# pc_sensything_lite_v1_2.net
KiCad netlist of a schematic drawn in EAGLE
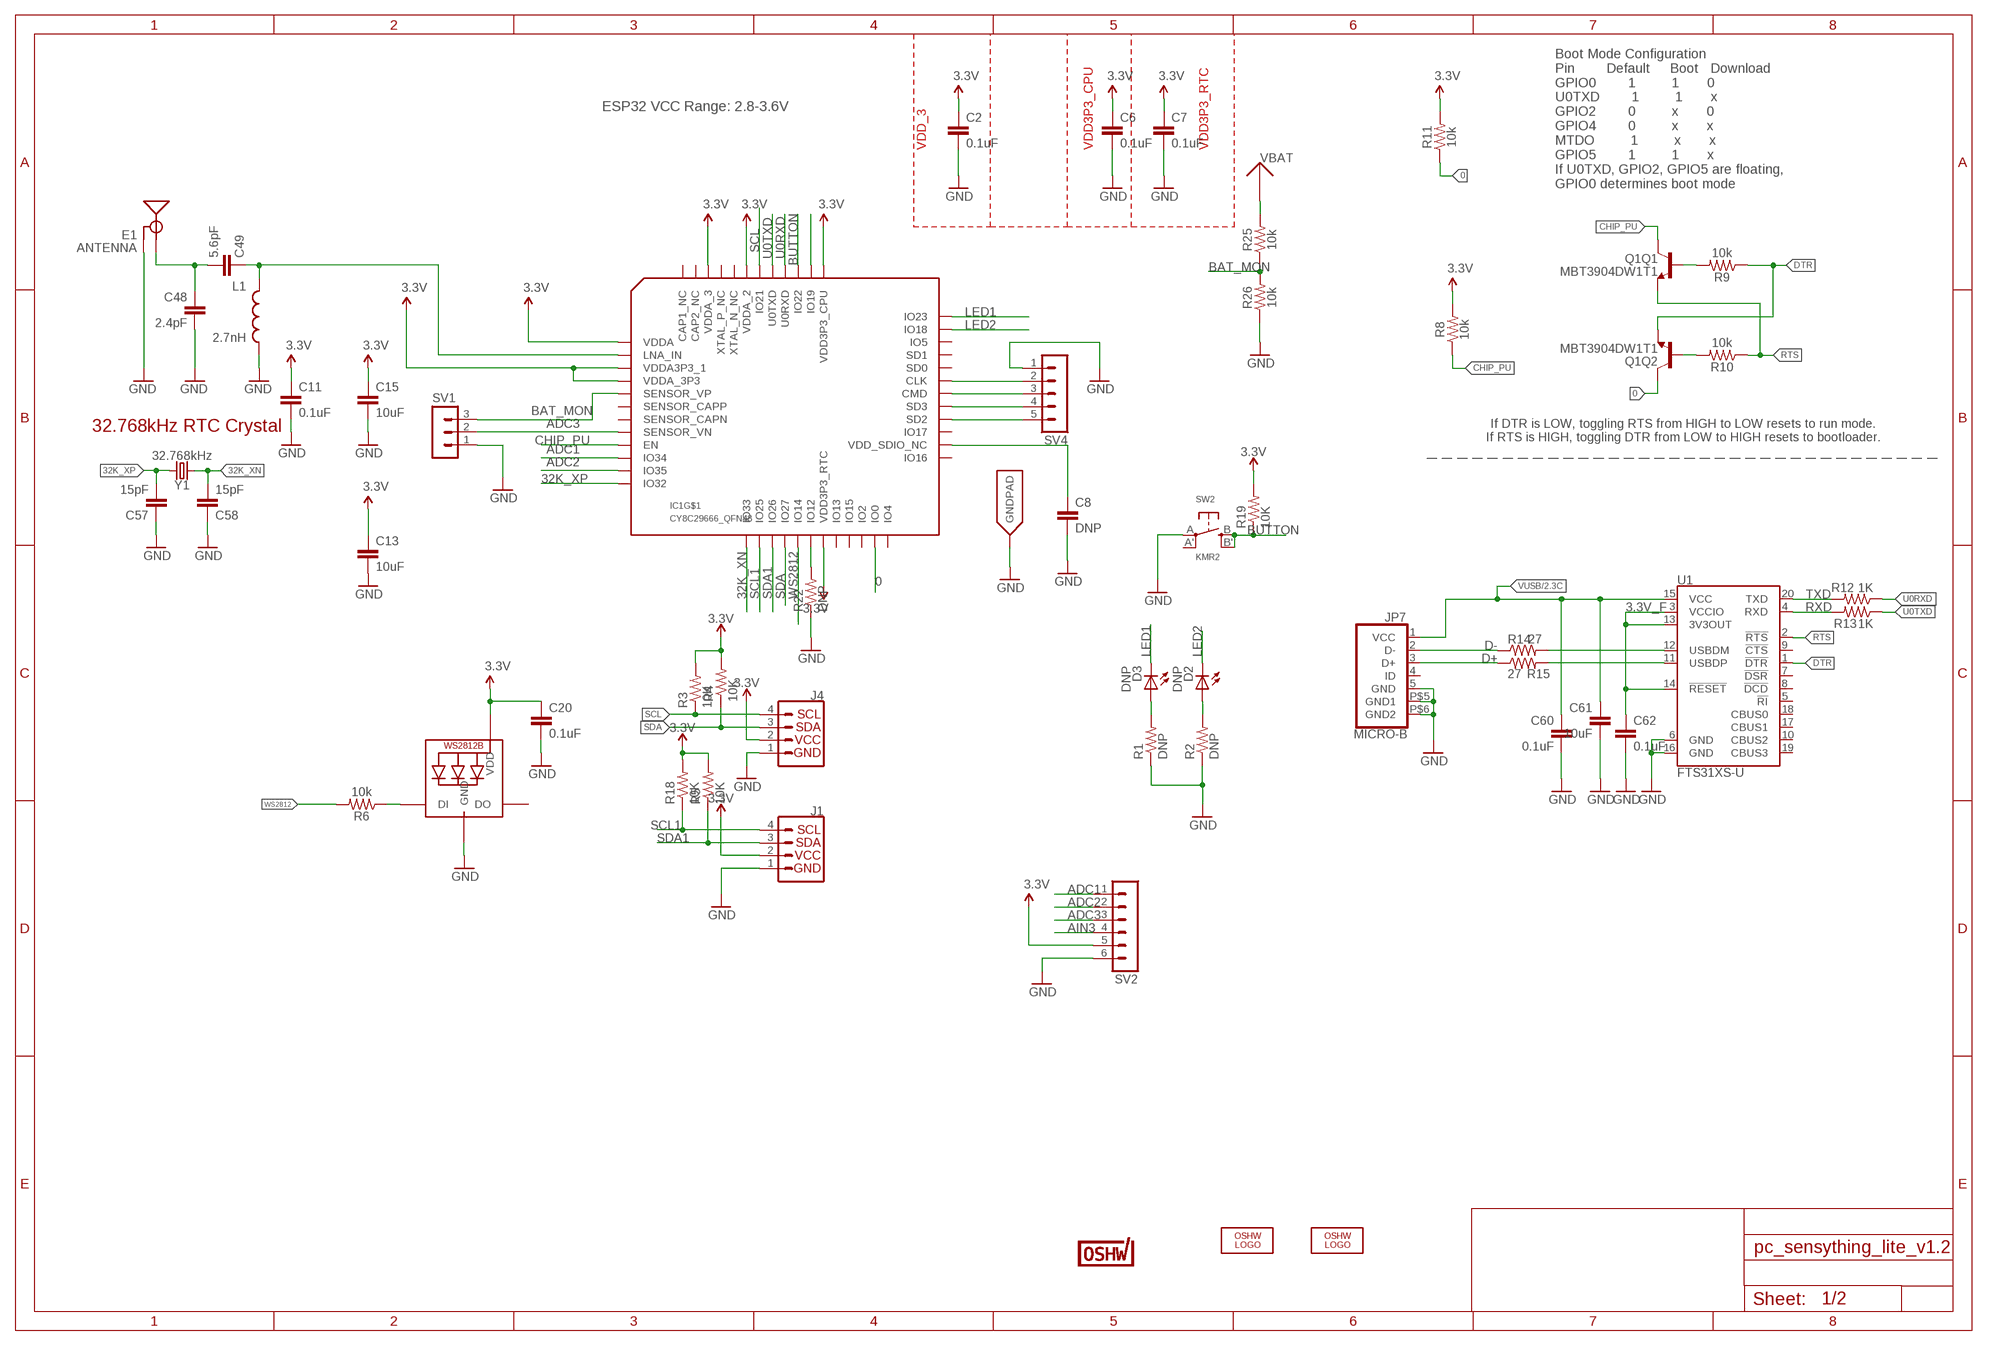
[diagram p0: schematic, sheet 1]
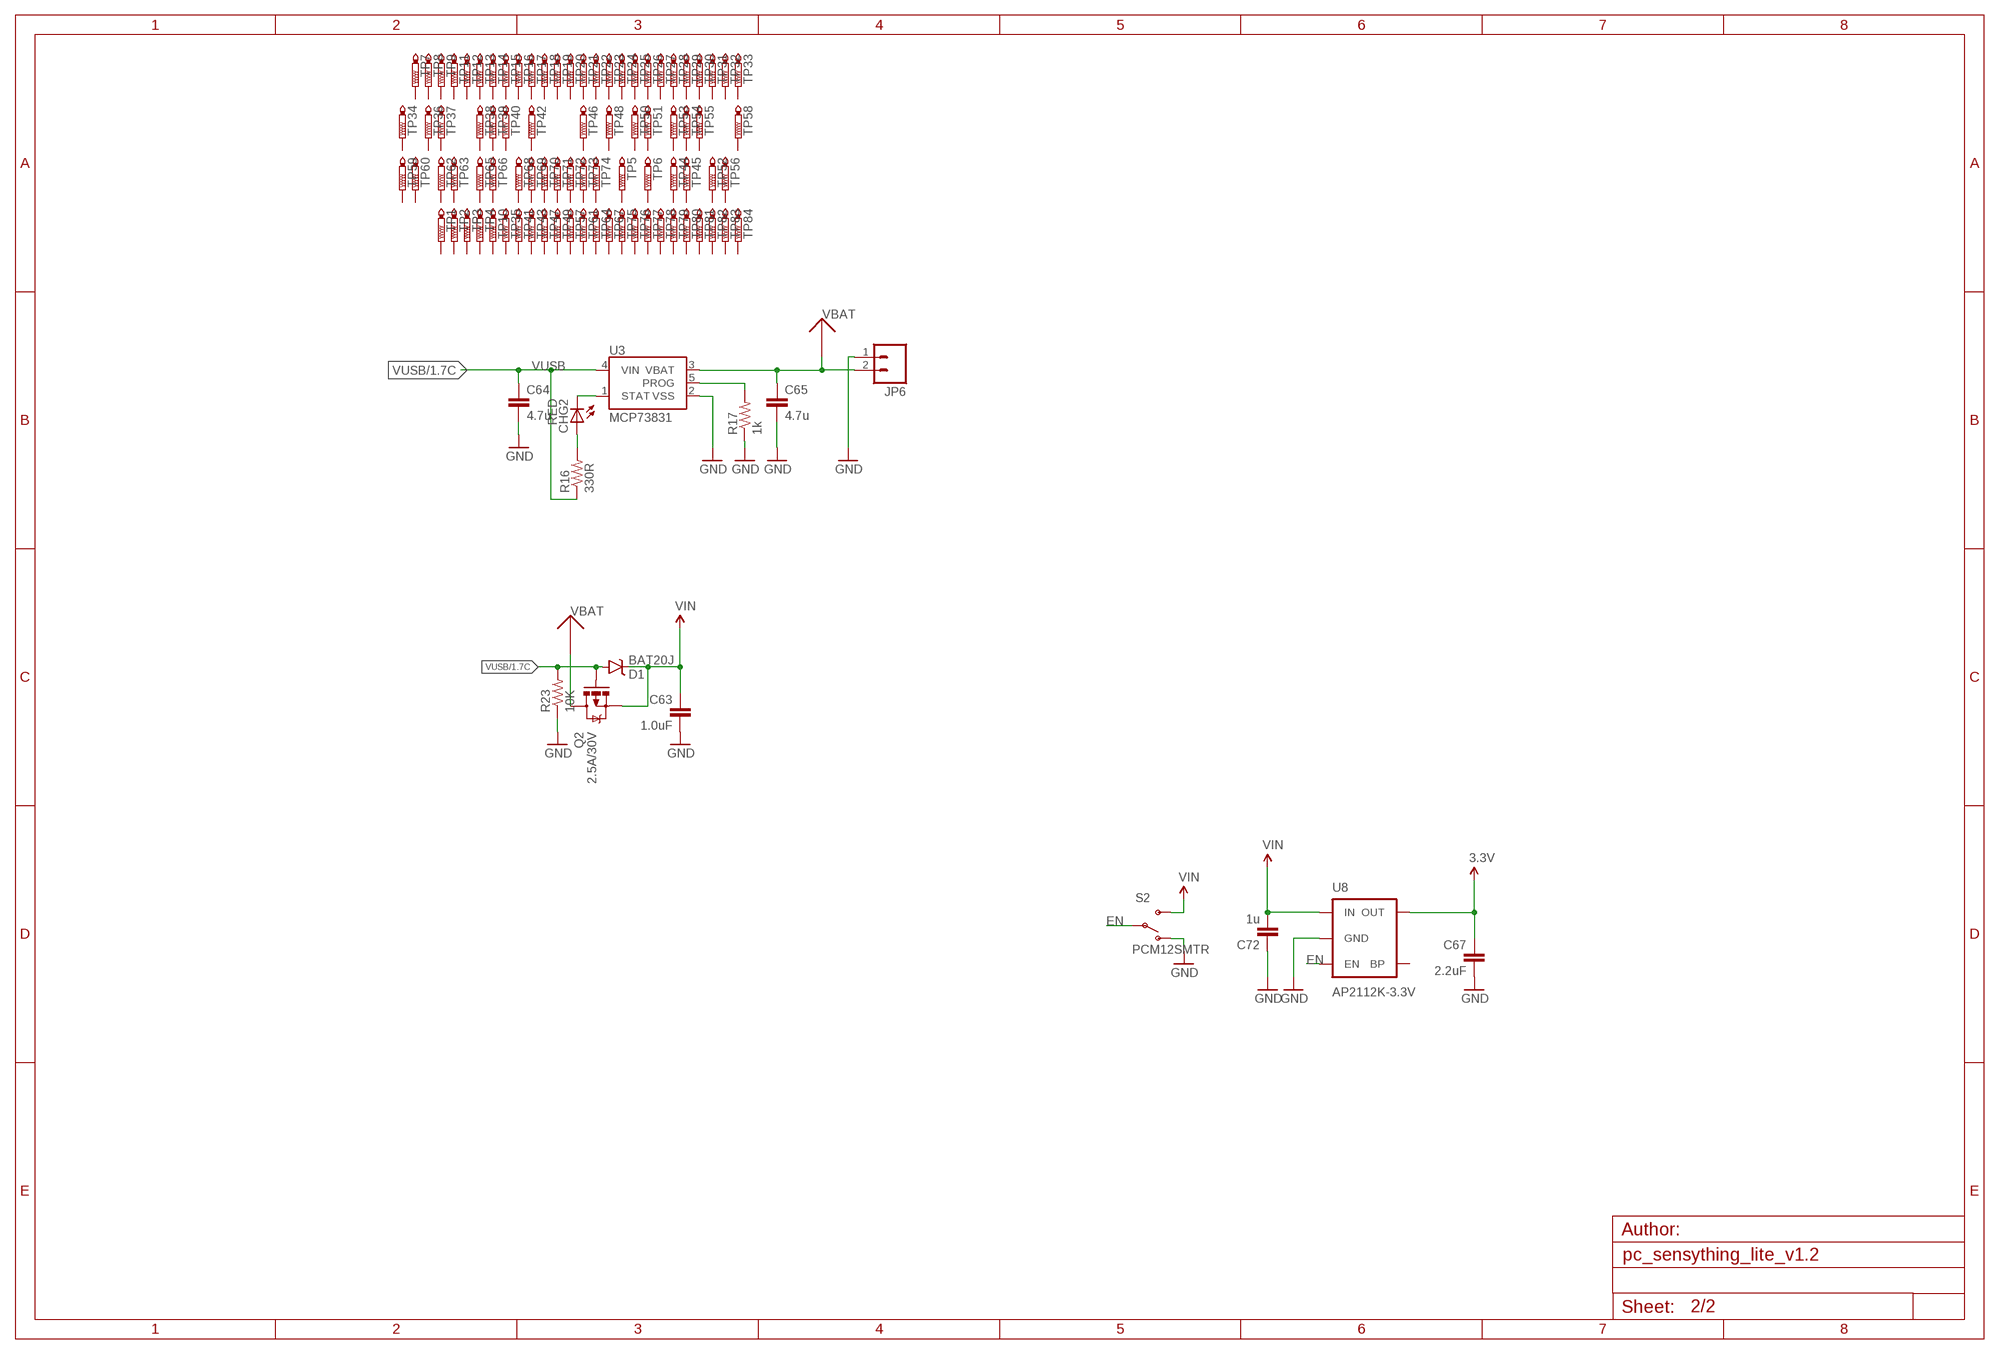
[diagram p1: schematic, sheet 2]

(export (version "E")
  (design (tool "Eeschema 10.0.6"))
  (components
    (comp (ref "C63")
      (value "1.0uF")
      (footprint "eagle-import:C0402")
      (libsource (lib "eagle-import") (part "C-EUC0402"))
    )
    (comp (ref "C64")
      (value "4.7u")
      (footprint "eagle-import:C0805")
      (libsource (lib "eagle-import") (part "C-EUC0805"))
    )
    (comp (ref "C65")
      (value "4.7u")
      (footprint "eagle-import:C0805")
      (libsource (lib "eagle-import") (part "C-EUC0805"))
    )
    (comp (ref "C67")
      (value "2.2uF")
      (footprint "eagle-import:C0402")
      (libsource (lib "eagle-import") (part "C-EUC0402"))
    )
    (comp (ref "C72")
      (value "1u")
      (footprint "eagle-import:C0402")
      (libsource (lib "eagle-import") (part "C-EUC0402"))
    )
    (comp (ref "CHG2")
      (value "RED")
      (footprint "eagle-import:CHIPLED_0603")
      (libsource (lib "eagle-import") (part "LEDCHIPLED_0603"))
    )
    (comp (ref "D1")
      (value "BAT20J")
      (footprint "eagle-import:SOD-323")
      (libsource (lib "eagle-import") (part "DIODE-SCHOTTKY-BAT20J"))
    )
    (comp (ref "JP6")
      (value "M02-JST-2MM-SMT")
      (footprint "eagle-import:JST-2-SMD")
      (libsource (lib "eagle-import") (part "M02-JST-2MM-SMT"))
    )
    (comp (ref "Q2")
      (value "2.5A/30V")
      (footprint "eagle-import:SOT23-3")
      (libsource (lib "eagle-import") (part "MOSFET-PCHANNELDMG2307L"))
    )
    (comp (ref "R16")
      (value "330R")
      (footprint "eagle-import:R0402")
      (libsource (lib "eagle-import") (part "R-US_R0402"))
    )
    (comp (ref "R17")
      (value "1k")
      (footprint "eagle-import:R0402")
      (libsource (lib "eagle-import") (part "R-US_R0402"))
    )
    (comp (ref "R23")
      (value "10K")
      (footprint "eagle-import:R0402")
      (libsource (lib "eagle-import") (part "R-US_R0402"))
    )
    (comp (ref "S2")
      (value "PCM12SMTR")
      (footprint "eagle-import:SWITCH-SPST-SMD-A")
      (libsource (lib "eagle-import") (part "SWITCH-SPDT-SMD-A"))
    )
    (comp (ref "TP1")
      (value "PTR1PAD1-13")
      (footprint "eagle-import:P1-13")
      (libsource (lib "eagle-import") (part "PTR1PAD1-13"))
    )
    (comp (ref "TP2")
      (value "PTR1PAD1-13")
      (footprint "eagle-import:P1-13")
      (libsource (lib "eagle-import") (part "PTR1PAD1-13"))
    )
    (comp (ref "TP3")
      (value "PTR1PAD1-13")
      (footprint "eagle-import:P1-13")
      (libsource (lib "eagle-import") (part "PTR1PAD1-13"))
    )
    (comp (ref "TP4")
      (value "PTR1PAD1-13")
      (footprint "eagle-import:P1-13")
      (libsource (lib "eagle-import") (part "PTR1PAD1-13"))
    )
    (comp (ref "TP5")
      (value "PTR1PAD1-13")
      (footprint "eagle-import:P1-13")
      (libsource (lib "eagle-import") (part "PTR1PAD1-13"))
    )
    (comp (ref "TP6")
      (value "PTR1PAD1-13")
      (footprint "eagle-import:P1-13")
      (libsource (lib "eagle-import") (part "PTR1PAD1-13"))
    )
    (comp (ref "TP7")
      (value "PTR1PAD1-13")
      (footprint "eagle-import:P1-13")
      (libsource (lib "eagle-import") (part "PTR1PAD1-13"))
    )
    (comp (ref "TP8")
      (value "PTR1PAD1-13")
      (footprint "eagle-import:P1-13")
      (libsource (lib "eagle-import") (part "PTR1PAD1-13"))
    )
    (comp (ref "TP9")
      (value "PTR1PAD1-13")
      (footprint "eagle-import:P1-13")
      (libsource (lib "eagle-import") (part "PTR1PAD1-13"))
    )
    (comp (ref "TP10")
      (value "PTR1PAD1-13")
      (footprint "eagle-import:P1-13")
      (libsource (lib "eagle-import") (part "PTR1PAD1-13"))
    )
    (comp (ref "TP11")
      (value "PTR1PAD1-13")
      (footprint "eagle-import:P1-13")
      (libsource (lib "eagle-import") (part "PTR1PAD1-13"))
    )
    (comp (ref "TP12")
      (value "PTR1PAD1-13")
      (footprint "eagle-import:P1-13")
      (libsource (lib "eagle-import") (part "PTR1PAD1-13"))
    )
    (comp (ref "TP13")
      (value "PTR1PAD1-13")
      (footprint "eagle-import:P1-13")
      (libsource (lib "eagle-import") (part "PTR1PAD1-13"))
    )
    (comp (ref "TP14")
      (value "PTR1PAD1-13")
      (footprint "eagle-import:P1-13")
      (libsource (lib "eagle-import") (part "PTR1PAD1-13"))
    )
    (comp (ref "TP15")
      (value "PTR1PAD1-13")
      (footprint "eagle-import:P1-13")
      (libsource (lib "eagle-import") (part "PTR1PAD1-13"))
    )
    (comp (ref "TP16")
      (value "PTR1PAD1-13")
      (footprint "eagle-import:P1-13")
      (libsource (lib "eagle-import") (part "PTR1PAD1-13"))
    )
    (comp (ref "TP17")
      (value "PTR1PAD1-13")
      (footprint "eagle-import:P1-13")
      (libsource (lib "eagle-import") (part "PTR1PAD1-13"))
    )
    (comp (ref "TP18")
      (value "PTR1PAD1-13")
      (footprint "eagle-import:P1-13")
      (libsource (lib "eagle-import") (part "PTR1PAD1-13"))
    )
    (comp (ref "TP19")
      (value "PTR1PAD1-13")
      (footprint "eagle-import:P1-13")
      (libsource (lib "eagle-import") (part "PTR1PAD1-13"))
    )
    (comp (ref "TP20")
      (value "PTR1PAD1-13")
      (footprint "eagle-import:P1-13")
      (libsource (lib "eagle-import") (part "PTR1PAD1-13"))
    )
    (comp (ref "TP21")
      (value "PTR1PAD1-13")
      (footprint "eagle-import:P1-13")
      (libsource (lib "eagle-import") (part "PTR1PAD1-13"))
    )
    (comp (ref "TP22")
      (value "PTR1PAD1-13")
      (footprint "eagle-import:P1-13")
      (libsource (lib "eagle-import") (part "PTR1PAD1-13"))
    )
    (comp (ref "TP23")
      (value "PTR1PAD1-13")
      (footprint "eagle-import:P1-13")
      (libsource (lib "eagle-import") (part "PTR1PAD1-13"))
    )
    (comp (ref "TP24")
      (value "PTR1PAD1-13")
      (footprint "eagle-import:P1-13")
      (libsource (lib "eagle-import") (part "PTR1PAD1-13"))
    )
    (comp (ref "TP25")
      (value "PTR1PAD1-13")
      (footprint "eagle-import:P1-13")
      (libsource (lib "eagle-import") (part "PTR1PAD1-13"))
    )
    (comp (ref "TP26")
      (value "PTR1PAD1-13")
      (footprint "eagle-import:P1-13")
      (libsource (lib "eagle-import") (part "PTR1PAD1-13"))
    )
    (comp (ref "TP27")
      (value "PTR1PAD1-13")
      (footprint "eagle-import:P1-13")
      (libsource (lib "eagle-import") (part "PTR1PAD1-13"))
    )
    (comp (ref "TP28")
      (value "PTR1PAD1-13")
      (footprint "eagle-import:P1-13")
      (libsource (lib "eagle-import") (part "PTR1PAD1-13"))
    )
    (comp (ref "TP29")
      (value "PTR1PAD1-13")
      (footprint "eagle-import:P1-13")
      (libsource (lib "eagle-import") (part "PTR1PAD1-13"))
    )
    (comp (ref "TP30")
      (value "PTR1PAD1-13")
      (footprint "eagle-import:P1-13")
      (libsource (lib "eagle-import") (part "PTR1PAD1-13"))
    )
    (comp (ref "TP31")
      (value "PTR1PAD1-13")
      (footprint "eagle-import:P1-13")
      (libsource (lib "eagle-import") (part "PTR1PAD1-13"))
    )
    (comp (ref "TP32")
      (value "PTR1PAD1-13")
      (footprint "eagle-import:P1-13")
      (libsource (lib "eagle-import") (part "PTR1PAD1-13"))
    )
    (comp (ref "TP33")
      (value "PTR1PAD1-13")
      (footprint "eagle-import:P1-13")
      (libsource (lib "eagle-import") (part "PTR1PAD1-13"))
    )
    (comp (ref "TP34")
      (value "PTR1PAD1-13")
      (footprint "eagle-import:P1-13")
      (libsource (lib "eagle-import") (part "PTR1PAD1-13"))
    )
    (comp (ref "TP35")
      (value "PTR1PAD1-13")
      (footprint "eagle-import:P1-13")
      (libsource (lib "eagle-import") (part "PTR1PAD1-13"))
    )
    (comp (ref "TP36")
      (value "PTR1PAD1-13")
      (footprint "eagle-import:P1-13")
      (libsource (lib "eagle-import") (part "PTR1PAD1-13"))
    )
    (comp (ref "TP37")
      (value "PTR1PAD1-13")
      (footprint "eagle-import:P1-13")
      (libsource (lib "eagle-import") (part "PTR1PAD1-13"))
    )
    (comp (ref "TP38")
      (value "PTR1PAD1-13")
      (footprint "eagle-import:P1-13")
      (libsource (lib "eagle-import") (part "PTR1PAD1-13"))
    )
    (comp (ref "TP39")
      (value "PTR1PAD1-13")
      (footprint "eagle-import:P1-13")
      (libsource (lib "eagle-import") (part "PTR1PAD1-13"))
    )
    (comp (ref "TP40")
      (value "PTR1PAD1-13")
      (footprint "eagle-import:P1-13")
      (libsource (lib "eagle-import") (part "PTR1PAD1-13"))
    )
    (comp (ref "TP41")
      (value "PTR1PAD1-13")
      (footprint "eagle-import:P1-13")
      (libsource (lib "eagle-import") (part "PTR1PAD1-13"))
    )
    (comp (ref "TP42")
      (value "PTR1PAD1-13")
      (footprint "eagle-import:P1-13")
      (libsource (lib "eagle-import") (part "PTR1PAD1-13"))
    )
    (comp (ref "TP43")
      (value "PTR1PAD1-13")
      (footprint "eagle-import:P1-13")
      (libsource (lib "eagle-import") (part "PTR1PAD1-13"))
    )
    (comp (ref "TP44")
      (value "PTR1PAD1-13")
      (footprint "eagle-import:P1-13")
      (libsource (lib "eagle-import") (part "PTR1PAD1-13"))
    )
    (comp (ref "TP45")
      (value "PTR1PAD1-13")
      (footprint "eagle-import:P1-13")
      (libsource (lib "eagle-import") (part "PTR1PAD1-13"))
    )
    (comp (ref "TP46")
      (value "PTR1PAD1-13")
      (footprint "eagle-import:P1-13")
      (libsource (lib "eagle-import") (part "PTR1PAD1-13"))
    )
    (comp (ref "TP47")
      (value "PTR1PAD1-13")
      (footprint "eagle-import:P1-13")
      (libsource (lib "eagle-import") (part "PTR1PAD1-13"))
    )
    (comp (ref "TP48")
      (value "PTR1PAD1-13")
      (footprint "eagle-import:P1-13")
      (libsource (lib "eagle-import") (part "PTR1PAD1-13"))
    )
    (comp (ref "TP49")
      (value "PTR1PAD1-13")
      (footprint "eagle-import:P1-13")
      (libsource (lib "eagle-import") (part "PTR1PAD1-13"))
    )
    (comp (ref "TP50")
      (value "PTR1PAD1-13")
      (footprint "eagle-import:P1-13")
      (libsource (lib "eagle-import") (part "PTR1PAD1-13"))
    )
    (comp (ref "TP51")
      (value "PTR1PAD1-13")
      (footprint "eagle-import:P1-13")
      (libsource (lib "eagle-import") (part "PTR1PAD1-13"))
    )
    (comp (ref "TP52")
      (value "PTR1PAD1-13")
      (footprint "eagle-import:P1-13")
      (libsource (lib "eagle-import") (part "PTR1PAD1-13"))
    )
    (comp (ref "TP53")
      (value "PTR1PAD1-13")
      (footprint "eagle-import:P1-13")
      (libsource (lib "eagle-import") (part "PTR1PAD1-13"))
    )
    (comp (ref "TP54")
      (value "PTR1PAD1-13")
      (footprint "eagle-import:P1-13")
      (libsource (lib "eagle-import") (part "PTR1PAD1-13"))
    )
    (comp (ref "TP55")
      (value "PTR1PAD1-13")
      (footprint "eagle-import:P1-13")
      (libsource (lib "eagle-import") (part "PTR1PAD1-13"))
    )
    (comp (ref "TP56")
      (value "PTR1PAD1-13")
      (footprint "eagle-import:P1-13")
      (libsource (lib "eagle-import") (part "PTR1PAD1-13"))
    )
    (comp (ref "TP57")
      (value "PTR1PAD1-13")
      (footprint "eagle-import:P1-13")
      (libsource (lib "eagle-import") (part "PTR1PAD1-13"))
    )
    (comp (ref "TP58")
      (value "PTR1PAD1-13")
      (footprint "eagle-import:P1-13")
      (libsource (lib "eagle-import") (part "PTR1PAD1-13"))
    )
    (comp (ref "TP59")
      (value "PTR1PAD1-13")
      (footprint "eagle-import:P1-13")
      (libsource (lib "eagle-import") (part "PTR1PAD1-13"))
    )
    (comp (ref "TP60")
      (value "PTR1PAD1-13")
      (footprint "eagle-import:P1-13")
      (libsource (lib "eagle-import") (part "PTR1PAD1-13"))
    )
    (comp (ref "TP61")
      (value "PTR1PAD1-13")
      (footprint "eagle-import:P1-13")
      (libsource (lib "eagle-import") (part "PTR1PAD1-13"))
    )
    (comp (ref "TP62")
      (value "PTR1PAD1-13")
      (footprint "eagle-import:P1-13")
      (libsource (lib "eagle-import") (part "PTR1PAD1-13"))
    )
    (comp (ref "TP63")
      (value "PTR1PAD1-13")
      (footprint "eagle-import:P1-13")
      (libsource (lib "eagle-import") (part "PTR1PAD1-13"))
    )
    (comp (ref "TP64")
      (value "PTR1PAD1-13")
      (footprint "eagle-import:P1-13")
      (libsource (lib "eagle-import") (part "PTR1PAD1-13"))
    )
    (comp (ref "TP65")
      (value "PTR1PAD1-13")
      (footprint "eagle-import:P1-13")
      (libsource (lib "eagle-import") (part "PTR1PAD1-13"))
    )
    (comp (ref "TP66")
      (value "PTR1PAD1-13")
      (footprint "eagle-import:P1-13")
      (libsource (lib "eagle-import") (part "PTR1PAD1-13"))
    )
    (comp (ref "TP67")
      (value "PTR1PAD1-13")
      (footprint "eagle-import:P1-13")
      (libsource (lib "eagle-import") (part "PTR1PAD1-13"))
    )
    (comp (ref "TP68")
      (value "PTR1PAD1-13")
      (footprint "eagle-import:P1-13")
      (libsource (lib "eagle-import") (part "PTR1PAD1-13"))
    )
    (comp (ref "TP69")
      (value "PTR1PAD1-13")
      (footprint "eagle-import:P1-13")
      (libsource (lib "eagle-import") (part "PTR1PAD1-13"))
    )
    (comp (ref "TP70")
      (value "PTR1PAD1-13")
      (footprint "eagle-import:P1-13")
      (libsource (lib "eagle-import") (part "PTR1PAD1-13"))
    )
    (comp (ref "TP71")
      (value "PTR1PAD1-13")
      (footprint "eagle-import:P1-13")
      (libsource (lib "eagle-import") (part "PTR1PAD1-13"))
    )
    (comp (ref "TP72")
      (value "PTR1PAD1-13")
      (footprint "eagle-import:P1-13")
      (libsource (lib "eagle-import") (part "PTR1PAD1-13"))
    )
    (comp (ref "TP73")
      (value "PTR1PAD1-13")
      (footprint "eagle-import:P1-13")
      (libsource (lib "eagle-import") (part "PTR1PAD1-13"))
    )
    (comp (ref "TP74")
      (value "PTR1PAD1-13")
      (footprint "eagle-import:P1-13")
      (libsource (lib "eagle-import") (part "PTR1PAD1-13"))
    )
    (comp (ref "TP75")
      (value "PTR1PAD1-13")
      (footprint "eagle-import:P1-13")
      (libsource (lib "eagle-import") (part "PTR1PAD1-13"))
    )
    (comp (ref "TP76")
      (value "PTR1PAD1-13")
      (footprint "eagle-import:P1-13")
      (libsource (lib "eagle-import") (part "PTR1PAD1-13"))
    )
    (comp (ref "TP77")
      (value "PTR1PAD1-13")
      (footprint "eagle-import:P1-13")
      (libsource (lib "eagle-import") (part "PTR1PAD1-13"))
    )
    (comp (ref "TP78")
      (value "PTR1PAD1-13")
      (footprint "eagle-import:P1-13")
      (libsource (lib "eagle-import") (part "PTR1PAD1-13"))
    )
    (comp (ref "TP79")
      (value "PTR1PAD1-13")
      (footprint "eagle-import:P1-13")
      (libsource (lib "eagle-import") (part "PTR1PAD1-13"))
    )
    (comp (ref "TP80")
      (value "PTR1PAD1-13")
      (footprint "eagle-import:P1-13")
      (libsource (lib "eagle-import") (part "PTR1PAD1-13"))
    )
    (comp (ref "TP81")
      (value "PTR1PAD1-13")
      (footprint "eagle-import:P1-13")
      (libsource (lib "eagle-import") (part "PTR1PAD1-13"))
    )
    (comp (ref "TP82")
      (value "PTR1PAD1-13")
      (footprint "eagle-import:P1-13")
      (libsource (lib "eagle-import") (part "PTR1PAD1-13"))
    )
    (comp (ref "TP83")
      (value "PTR1PAD1-13")
      (footprint "eagle-import:P1-13")
      (libsource (lib "eagle-import") (part "PTR1PAD1-13"))
    )
    (comp (ref "TP84")
      (value "PTR1PAD1-13")
      (footprint "eagle-import:P1-13")
      (libsource (lib "eagle-import") (part "PTR1PAD1-13"))
    )
    (comp (ref "U3")
      (value "MCP73831")
      (footprint "eagle-import:SOT23-5")
      (libsource (lib "eagle-import") (part "MCP73831"))
    )
    (comp (ref "U8")
      (value "AP2112K-3.3V")
      (footprint "eagle-import:SOT23-5")
      (libsource (lib "eagle-import") (part "V_REG_LDOSMD"))
    )
    (comp (ref "C2")
      (value "0.1uF")
      (footprint "eagle-import:0402")
      (libsource (lib "eagle-import") (part "0.1UF-0402-16V-10%"))
    )
    (comp (ref "C6")
      (value "0.1uF")
      (footprint "eagle-import:0402")
      (libsource (lib "eagle-import") (part "0.1UF-0402-16V-10%"))
    )
    (comp (ref "C7")
      (value "0.1uF")
      (footprint "eagle-import:0402")
      (libsource (lib "eagle-import") (part "0.1UF-0402-16V-10%"))
    )
    (comp (ref "C8")
      (value "DNP")
      (footprint "eagle-import:0603")
      (libsource (lib "eagle-import") (part "0.1UF-0603-25V-(+80/-20%)"))
    )
    (comp (ref "C11")
      (value "0.1uF")
      (footprint "eagle-import:0402")
      (libsource (lib "eagle-import") (part "0.1UF-0402-16V-10%"))
    )
    (comp (ref "C13")
      (value "10uF")
      (footprint "eagle-import:C0402")
      (libsource (lib "eagle-import") (part "C-EUC0402"))
    )
    (comp (ref "C15")
      (value "10uF")
      (footprint "eagle-import:0603")
      (libsource (lib "eagle-import") (part "10UF-0603-6.3V-20%"))
    )
    (comp (ref "C20")
      (value "0.1uF")
      (footprint "eagle-import:0603")
      (libsource (lib "eagle-import") (part "0.1UF-0603-25V-(+80/-20%)"))
    )
    (comp (ref "C48")
      (value "2.4pF")
      (footprint "eagle-import:0603")
      (libsource (lib "eagle-import") (part "2.4PF-0603-50V-5%"))
    )
    (comp (ref "C49")
      (value "5.6pF")
      (footprint "eagle-import:0603")
      (libsource (lib "eagle-import") (part "5.6PF-50V-5%(0603)"))
    )
    (comp (ref "C57")
      (value "15pF")
      (footprint "eagle-import:0603")
      (libsource (lib "eagle-import") (part "15PF-0603-50V-5%"))
    )
    (comp (ref "C58")
      (value "15pF")
      (footprint "eagle-import:0603")
      (libsource (lib "eagle-import") (part "15PF-0603-50V-5%"))
    )
    (comp (ref "C60")
      (value "0.1uF")
      (footprint "eagle-import:C0402")
      (libsource (lib "eagle-import") (part "C-EUC0402"))
    )
    (comp (ref "C61")
      (value "10uF")
      (footprint "eagle-import:C0805")
      (libsource (lib "eagle-import") (part "C-EUC0805"))
    )
    (comp (ref "C62")
      (value "0.1uF")
      (footprint "eagle-import:C0402")
      (libsource (lib "eagle-import") (part "C-EUC0402"))
    )
    (comp (ref "D2")
      (value "DNP")
      (footprint "eagle-import:CHIPLED_0603")
      (libsource (lib "eagle-import") (part "LEDCHIPLED_0603"))
    )
    (comp (ref "D3")
      (value "DNP")
      (footprint "eagle-import:CHIPLED_0603")
      (libsource (lib "eagle-import") (part "LEDCHIPLED_0603"))
    )
    (comp (ref "E1")
      (value "ANTENNA")
      (footprint "eagle-import:TRACE_ANTENNA_2.4GHZ_25.7MM_TUNED")
      (libsource (lib "eagle-import") (part "ANTENNATRACE-TUNED"))
    )
    (comp (ref "IC1")
      (value "CY8C29666_QFN48")
      (footprint "eagle-import:QFN48")
      (libsource (lib "eagle-import") (part "CY8C29666_QFN48"))
    )
    (comp (ref "J1")
      (value "QWIIC_CONNECTORJS-1MM")
      (footprint "eagle-import:1X04_1MM_RA")
      (libsource (lib "eagle-import") (part "QWIIC_CONNECTORJS-1MM"))
    )
    (comp (ref "J4")
      (value "QWIIC_CONNECTORJS-1MM")
      (footprint "eagle-import:1X04_1MM_RA")
      (libsource (lib "eagle-import") (part "QWIIC_CONNECTORJS-1MM"))
    )
    (comp (ref "JP7")
      (value "MICRO-B")
      (footprint "eagle-import:MICRO-B")
      (libsource (lib "eagle-import") (part "MICRO-B"))
    )
    (comp (ref "L1")
      (value "2.7nH")
      (footprint "eagle-import:0603")
      (libsource (lib "eagle-import") (part "INDUCTOR0603"))
    )
    (comp (ref "LED1")
      (value "WS2812B5050")
      (footprint "eagle-import:WS2812B")
      (libsource (lib "eagle-import") (part "WS2812B5050"))
    )
    (comp (ref "LOGO1")
      (value "OSHW_LOGO_FILLX0200-NT")
      (footprint "eagle-import:OSHW_FILLX200_NOTEXT")
      (libsource (lib "eagle-import") (part "OSHW_LOGO_FILLX0200-NT"))
    )
    (comp (ref "LOGO3")
      (value "OSHW_LOGO_FILLX0200-NT")
      (footprint "eagle-import:OSHW_FILLX200_NOTEXT")
      (libsource (lib "eagle-import") (part "OSHW_LOGO_FILLX0200-NT"))
    )
    (comp (ref "Q1")
      (value "MBT3904DW1T1")
      (footprint "eagle-import:SC70-6")
      (libsource (lib "eagle-import") (part "MBT3904DW1T1"))
    )
    (comp (ref "R1")
      (value "DNP")
      (footprint "eagle-import:R0402")
      (libsource (lib "eagle-import") (part "R-US_R0402"))
    )
    (comp (ref "R2")
      (value "DNP")
      (footprint "eagle-import:R0402")
      (libsource (lib "eagle-import") (part "R-US_R0402"))
    )
    (comp (ref "R3")
      (value "10K")
      (footprint "eagle-import:R0402")
      (libsource (lib "eagle-import") (part "R-US_R0402"))
    )
    (comp (ref "R4")
      (value "10K")
      (footprint "eagle-import:R0402")
      (libsource (lib "eagle-import") (part "R-US_R0402"))
    )
    (comp (ref "R5")
      (value "10K")
      (footprint "eagle-import:R0402")
      (libsource (lib "eagle-import") (part "R-US_R0402"))
    )
    (comp (ref "R6")
      (value "10k")
      (footprint "eagle-import:0603")
      (libsource (lib "eagle-import") (part "10KOHM-1/10W-1%(0603)0603"))
    )
    (comp (ref "R8")
      (value "10k")
      (footprint "eagle-import:0603")
      (libsource (lib "eagle-import") (part "10KOHM-1/10W-1%(0603)0603"))
    )
    (comp (ref "R9")
      (value "10k")
      (footprint "eagle-import:0603")
      (libsource (lib "eagle-import") (part "10KOHM-0603-1/10W-1%"))
    )
    (comp (ref "R10")
      (value "10k")
      (footprint "eagle-import:0603")
      (libsource (lib "eagle-import") (part "10KOHM-0603-1/10W-1%"))
    )
    (comp (ref "R11")
      (value "10k")
      (footprint "eagle-import:0603")
      (libsource (lib "eagle-import") (part "10KOHM-1/10W-1%(0603)0603"))
    )
    (comp (ref "R12")
      (value "1K")
      (footprint "eagle-import:R0402")
      (libsource (lib "eagle-import") (part "R-US_R0402"))
    )
    (comp (ref "R13")
      (value "1K")
      (footprint "eagle-import:R0402")
      (libsource (lib "eagle-import") (part "R-US_R0402"))
    )
    (comp (ref "R14")
      (value "27")
      (footprint "eagle-import:R0402")
      (libsource (lib "eagle-import") (part "R-US_R0402"))
    )
    (comp (ref "R15")
      (value "27")
      (footprint "eagle-import:R0402")
      (libsource (lib "eagle-import") (part "R-US_R0402"))
    )
    (comp (ref "R18")
      (value "10K")
      (footprint "eagle-import:R0402")
      (libsource (lib "eagle-import") (part "R-US_R0402"))
    )
    (comp (ref "R19")
      (value "10K")
      (footprint "eagle-import:R0402")
      (libsource (lib "eagle-import") (part "R-US_R0402"))
    )
    (comp (ref "R22")
      (value "DNP")
      (footprint "eagle-import:R0402")
      (libsource (lib "eagle-import") (part "R-US_R0402"))
    )
    (comp (ref "R25")
      (value "10k")
      (footprint "eagle-import:0603")
      (libsource (lib "eagle-import") (part "10KOHM-1/10W-1%(0603)0603"))
    )
    (comp (ref "R26")
      (value "10k")
      (footprint "eagle-import:0603")
      (libsource (lib "eagle-import") (part "10KOHM-1/10W-1%(0603)0603"))
    )
    (comp (ref "SV1")
      (value "MA03-1")
      (footprint "eagle-import:MA03-1")
      (libsource (lib "eagle-import") (part "MA03-1"))
    )
    (comp (ref "SV2")
      (value "MA06-1")
      (footprint "eagle-import:MA06-1")
      (libsource (lib "eagle-import") (part "MA06-1"))
    )
    (comp (ref "SV4")
      (value "MA05-1")
      (footprint "eagle-import:MA05-1")
      (libsource (lib "eagle-import") (part "MA05-1"))
    )
    (comp (ref "SW2")
      (value "KMR2")
      (footprint "eagle-import:BTN_KMR2_4.6X2.8")
      (libsource (lib "eagle-import") (part "SWITCH_TACT_SMT4.6X2.8"))
    )
    (comp (ref "U$22")
      (value "CERT-SMALL")
      (footprint "eagle-import:CERT-SMALL-SILK")
      (libsource (lib "eagle-import") (part "CERT-SMALL"))
    )
    (comp (ref "U1")
      (value "FTS31XS-U")
      (footprint "eagle-import:SSOP20_L")
      (libsource (lib "eagle-import") (part "FT231XS"))
    )
    (comp (ref "Y1")
      (value "32.768kHz")
      (footprint "eagle-import:CRYSTAL-SMD-3.2X1.5MM")
      (libsource (lib "eagle-import") (part "CRYSTAL-32.768KHZSMD-3.2X1.5"))
    )
  )
  (nets
    (net (code "1") (name "0") (class "Default")
      (node (ref "IC1") (pin "23") (pinfunction "IO0_23") (pintype "bidirectional"))
      (node (ref "Q1") (pin "6") (pinfunction "C_6") (pintype "passive"))
      (node (ref "R11") (pin "1") (pinfunction "1_1") (pintype "passive"))
    )
    (net (code "2") (name "3.3V") (class "Default")
      (node (ref "C11") (pin "1") (pinfunction "1_1") (pintype "passive"))
      (node (ref "C13") (pin "1") (pinfunction "1_1") (pintype "passive"))
      (node (ref "C15") (pin "1") (pinfunction "1_1") (pintype "passive"))
      (node (ref "C2") (pin "1") (pinfunction "1_1") (pintype "passive"))
      (node (ref "C20") (pin "1") (pinfunction "1_1") (pintype "passive"))
      (node (ref "C6") (pin "1") (pinfunction "1_1") (pintype "passive"))
      (node (ref "C67") (pin "1") (pinfunction "1_1") (pintype "passive"))
      (node (ref "C7") (pin "1") (pinfunction "1_1") (pintype "passive"))
      (node (ref "IC1") (pin "1") (pinfunction "VDDA_1") (pintype "bidirectional"))
      (node (ref "IC1") (pin "19") (pinfunction "VDD3P3_RTC_19") (pintype "bidirectional"))
      (node (ref "IC1") (pin "3") (pinfunction "VDDA3P3_1_3") (pintype "bidirectional"))
      (node (ref "IC1") (pin "37") (pinfunction "VDD3P3_CPU_37") (pintype "bidirectional"))
      (node (ref "IC1") (pin "4") (pinfunction "VDDA_3P3_4") (pintype "bidirectional"))
      (node (ref "IC1") (pin "43") (pinfunction "VDDA_2_43") (pintype "bidirectional"))
      (node (ref "IC1") (pin "46") (pinfunction "VDDA_3_46") (pintype "bidirectional"))
      (node (ref "J1") (pin "2") (pinfunction "2_2") (pintype "power_in"))
      (node (ref "J4") (pin "2") (pinfunction "2_2") (pintype "power_in"))
      (node (ref "LED1") (pin "1-VDD") (pinfunction "VDD_1-VDD") (pintype "power_in"))
      (node (ref "R11") (pin "2") (pinfunction "2_2") (pintype "passive"))
      (node (ref "R18") (pin "2") (pinfunction "2_2") (pintype "passive"))
      (node (ref "R19") (pin "2") (pinfunction "2_2") (pintype "passive"))
      (node (ref "R3") (pin "2") (pinfunction "2_2") (pintype "passive"))
      (node (ref "R4") (pin "2") (pinfunction "2_2") (pintype "passive"))
      (node (ref "R5") (pin "2") (pinfunction "2_2") (pintype "passive"))
      (node (ref "R8") (pin "2") (pinfunction "2_2") (pintype "passive"))
      (node (ref "SV2") (pin "5") (pinfunction "5_5") (pintype "passive"))
      (node (ref "U8") (pin "5") (pinfunction "OUT_5") (pintype "passive"))
    )
    (net (code "3") (name "3.3V_F") (class "Default")
      (node (ref "C62") (pin "1") (pinfunction "1_1") (pintype "passive"))
      (node (ref "U1") (pin "13") (pinfunction "3V3OUT_13") (pintype "bidirectional"))
      (node (ref "U1") (pin "14") (pinfunction "~{RESET}_14") (pintype "bidirectional"))
      (node (ref "U1") (pin "3") (pinfunction "VCCIO_3") (pintype "bidirectional"))
    )
    (net (code "4") (name "32K_XN") (class "Default")
      (node (ref "C58") (pin "2") (pinfunction "2_2") (pintype "passive"))
      (node (ref "IC1") (pin "13") (pinfunction "IO33_13") (pintype "bidirectional"))
      (node (ref "Y1") (pin "P$2") (pinfunction "2_P$2") (pintype "passive"))
    )
    (net (code "5") (name "32K_XP") (class "Default")
      (node (ref "C57") (pin "2") (pinfunction "2_2") (pintype "passive"))
      (node (ref "IC1") (pin "12") (pinfunction "IO32_12") (pintype "bidirectional"))
      (node (ref "Y1") (pin "P$1") (pinfunction "1_P$1") (pintype "passive"))
    )
    (net (code "6") (name "ADC1") (class "Default")
      (node (ref "IC1") (pin "10") (pinfunction "IO34_10") (pintype "bidirectional"))
      (node (ref "SV2") (pin "1") (pinfunction "1_1") (pintype "passive"))
    )
    (net (code "7") (name "ADC2") (class "Default")
      (node (ref "IC1") (pin "11") (pinfunction "IO35_11") (pintype "bidirectional"))
      (node (ref "SV2") (pin "2") (pinfunction "2_2") (pintype "passive"))
    )
    (net (code "8") (name "ADC3") (class "Default")
      (node (ref "IC1") (pin "8") (pinfunction "SENSOR_VN_8") (pintype "bidirectional"))
      (node (ref "SV1") (pin "2") (pinfunction "2_2") (pintype "passive"))
      (node (ref "SV2") (pin "3") (pinfunction "3_3") (pintype "passive"))
    )
    (net (code "9") (name "AIN3") (class "Default")
      (node (ref "SV2") (pin "4") (pinfunction "4_4") (pintype "passive"))
    )
    (net (code "10") (name "BAT_MON") (class "Default")
      (node (ref "IC1") (pin "5") (pinfunction "SENSOR_VP_5") (pintype "bidirectional"))
      (node (ref "R25") (pin "1") (pinfunction "1_1") (pintype "passive"))
      (node (ref "R26") (pin "2") (pinfunction "2_2") (pintype "passive"))
      (node (ref "SV1") (pin "3") (pinfunction "3_3") (pintype "passive"))
    )
    (net (code "11") (name "BUTTON") (class "Default")
      (node (ref "IC1") (pin "39") (pinfunction "IO22_39") (pintype "bidirectional"))
      (node (ref "R19") (pin "1") (pinfunction "1_1") (pintype "passive"))
      (node (ref "SW2") (pin "B") (pinfunction "S_B") (pintype "passive"))
      (node (ref "SW2") (pin "B'") (pinfunction "S1_B'") (pintype "passive"))
    )
    (net (code "12") (name "CHIP_PU") (class "Default")
      (node (ref "IC1") (pin "9") (pinfunction "EN_9") (pintype "bidirectional"))
      (node (ref "Q1") (pin "3") (pinfunction "C_3") (pintype "passive"))
      (node (ref "R8") (pin "1") (pinfunction "1_1") (pintype "passive"))
    )
    (net (code "13") (name "D+") (class "Default")
      (node (ref "JP7") (pin "3") (pinfunction "D+_3") (pintype "bidirectional"))
      (node (ref "R15") (pin "1") (pinfunction "1_1") (pintype "passive"))
    )
    (net (code "14") (name "D-") (class "Default")
      (node (ref "JP7") (pin "2") (pinfunction "D-_2") (pintype "bidirectional"))
      (node (ref "R14") (pin "1") (pinfunction "1_1") (pintype "passive"))
    )
    (net (code "15") (name "DTR") (class "Default")
      (node (ref "Q1") (pin "1") (pinfunction "E_1") (pintype "passive"))
      (node (ref "R9") (pin "1") (pinfunction "1_1") (pintype "passive"))
      (node (ref "U1") (pin "1") (pinfunction "~{DTR}_1") (pintype "bidirectional"))
    )
    (net (code "16") (name "EN") (class "Default")
      (node (ref "S2") (pin "2") (pinfunction "P_2") (pintype "passive"))
      (node (ref "U8") (pin "3") (pinfunction "EN_3") (pintype "input"))
    )
    (net (code "17") (name "GND") (class "Default")
      (node (ref "C11") (pin "2") (pinfunction "2_2") (pintype "passive"))
      (node (ref "C13") (pin "2") (pinfunction "2_2") (pintype "passive"))
      (node (ref "C15") (pin "2") (pinfunction "2_2") (pintype "passive"))
      (node (ref "C2") (pin "2") (pinfunction "2_2") (pintype "passive"))
      (node (ref "C20") (pin "2") (pinfunction "2_2") (pintype "passive"))
      (node (ref "C48") (pin "2") (pinfunction "2_2") (pintype "passive"))
      (node (ref "C57") (pin "1") (pinfunction "1_1") (pintype "passive"))
      (node (ref "C58") (pin "1") (pinfunction "1_1") (pintype "passive"))
      (node (ref "C6") (pin "2") (pinfunction "2_2") (pintype "passive"))
      (node (ref "C60") (pin "2") (pinfunction "2_2") (pintype "passive"))
      (node (ref "C61") (pin "2") (pinfunction "2_2") (pintype "passive"))
      (node (ref "C62") (pin "2") (pinfunction "2_2") (pintype "passive"))
      (node (ref "C63") (pin "2") (pinfunction "2_2") (pintype "passive"))
      (node (ref "C64") (pin "2") (pinfunction "2_2") (pintype "passive"))
      (node (ref "C65") (pin "2") (pinfunction "2_2") (pintype "passive"))
      (node (ref "C67") (pin "2") (pinfunction "2_2") (pintype "passive"))
      (node (ref "C7") (pin "2") (pinfunction "2_2") (pintype "passive"))
      (node (ref "C72") (pin "1") (pinfunction "1_1") (pintype "passive"))
      (node (ref "C8") (pin "2") (pinfunction "2_2") (pintype "passive"))
      (node (ref "E1") (pin "GND") (pinfunction "GND_GND") (pintype "bidirectional"))
      (node (ref "E1") (pin "GND2") (pinfunction "GND_GND2") (pintype "bidirectional"))
      (node (ref "IC1") (pin "EXP") (pinfunction "GNDPAD_EXP") (pintype "power_in"))
      (node (ref "J1") (pin "1") (pinfunction "1_1") (pintype "power_in"))
      (node (ref "J4") (pin "1") (pinfunction "1_1") (pintype "power_in"))
      (node (ref "JP6") (pin "1") (pinfunction "1_1") (pintype "passive"))
      (node (ref "JP7") (pin "5") (pinfunction "GND_5") (pintype "bidirectional"))
      (node (ref "JP7") (pin "P$5") (pinfunction "GND1_P$5") (pintype "bidirectional"))
      (node (ref "JP7") (pin "P$6") (pinfunction "GND2_P$6") (pintype "bidirectional"))
      (node (ref "L1") (pin "2") (pinfunction "2_2") (pintype "passive"))
      (node (ref "LED1") (pin "3-GND") (pinfunction "GND_3-GND") (pintype "power_in"))
      (node (ref "R1") (pin "1") (pinfunction "1_1") (pintype "passive"))
      (node (ref "R17") (pin "1") (pinfunction "1_1") (pintype "passive"))
      (node (ref "R2") (pin "1") (pinfunction "1_1") (pintype "passive"))
      (node (ref "R22") (pin "1") (pinfunction "1_1") (pintype "passive"))
      (node (ref "R23") (pin "1") (pinfunction "1_1") (pintype "passive"))
      (node (ref "R26") (pin "1") (pinfunction "1_1") (pintype "passive"))
      (node (ref "S2") (pin "1") (pinfunction "O_1") (pintype "passive"))
      (node (ref "SV1") (pin "1") (pinfunction "1_1") (pintype "passive"))
      (node (ref "SV2") (pin "6") (pinfunction "6_6") (pintype "passive"))
      (node (ref "SV4") (pin "1") (pinfunction "1_1") (pintype "passive"))
      (node (ref "SW2") (pin "A") (pinfunction "P_A") (pintype "passive"))
      (node (ref "U1") (pin "16") (pinfunction "GND_16") (pintype "bidirectional"))
      (node (ref "U1") (pin "6") (pinfunction "GND_6") (pintype "bidirectional"))
      (node (ref "U3") (pin "2") (pinfunction "VSS_2") (pintype "power_in"))
      (node (ref "U8") (pin "2") (pinfunction "GND_2") (pintype "input"))
    )
    (net (code "18") (name "LED1") (class "Default")
      (node (ref "D3") (pin "C") (pinfunction "C_C") (pintype "passive"))
      (node (ref "IC1") (pin "36") (pinfunction "IO23_36") (pintype "bidirectional"))
    )
    (net (code "19") (name "LED2") (class "Default")
      (node (ref "D2") (pin "C") (pinfunction "C_C") (pintype "passive"))
      (node (ref "IC1") (pin "35") (pinfunction "IO18_35") (pintype "bidirectional"))
    )
    (net (code "20") (name "Net-(CHG2-PadA)") (class "Default")
      (node (ref "CHG2") (pin "A") (pinfunction "A_A") (pintype "passive"))
      (node (ref "R16") (pin "2") (pinfunction "2_2") (pintype "passive"))
    )
    (net (code "21") (name "Net-(D2-PadA)") (class "Default")
      (node (ref "D2") (pin "A") (pinfunction "A_A") (pintype "passive"))
      (node (ref "R2") (pin "2") (pinfunction "2_2") (pintype "passive"))
    )
    (net (code "22") (name "Net-(D3-PadA)") (class "Default")
      (node (ref "D3") (pin "A") (pinfunction "A_A") (pintype "passive"))
      (node (ref "R1") (pin "2") (pinfunction "2_2") (pintype "passive"))
    )
    (net (code "23") (name "Net-(E1-SIGNAL)") (class "Default")
      (node (ref "C48") (pin "1") (pinfunction "1_1") (pintype "passive"))
      (node (ref "C49") (pin "2") (pinfunction "2_2") (pintype "passive"))
      (node (ref "E1") (pin "ANT") (pinfunction "SIGNAL_ANT") (pintype "bidirectional"))
    )
    (net (code "24") (name "Net-(IC1A-CLK)") (class "Default")
      (node (ref "IC1") (pin "31") (pinfunction "CLK_31") (pintype "bidirectional"))
      (node (ref "SV4") (pin "2") (pinfunction "2_2") (pintype "passive"))
    )
    (net (code "25") (name "Net-(IC1A-CMD)") (class "Default")
      (node (ref "IC1") (pin "30") (pinfunction "CMD_30") (pintype "bidirectional"))
      (node (ref "SV4") (pin "3") (pinfunction "3_3") (pintype "passive"))
    )
    (net (code "26") (name "Net-(IC1A-IO12)") (class "Default")
      (node (ref "IC1") (pin "18") (pinfunction "IO12_18") (pintype "power_in"))
      (node (ref "R22") (pin "2") (pinfunction "2_2") (pintype "passive"))
    )
    (net (code "27") (name "Net-(IC1A-LNA_IN)") (class "Default")
      (node (ref "C49") (pin "1") (pinfunction "1_1") (pintype "passive"))
      (node (ref "IC1") (pin "2") (pinfunction "LNA_IN_2") (pintype "bidirectional"))
      (node (ref "L1") (pin "1") (pinfunction "1_1") (pintype "passive"))
    )
    (net (code "28") (name "Net-(IC1A-SD2)") (class "Default")
      (node (ref "IC1") (pin "28") (pinfunction "SD2_28") (pintype "bidirectional"))
      (node (ref "SV4") (pin "5") (pinfunction "5_5") (pintype "passive"))
    )
    (net (code "29") (name "Net-(IC1A-SD3)") (class "Default")
      (node (ref "IC1") (pin "29") (pinfunction "SD3_29") (pintype "bidirectional"))
      (node (ref "SV4") (pin "4") (pinfunction "4_4") (pintype "passive"))
    )
    (net (code "30") (name "Net-(IC1A-VDD_SDIO_NC)") (class "Default")
      (node (ref "C8") (pin "1") (pinfunction "1_1") (pintype "passive"))
      (node (ref "IC1") (pin "26") (pinfunction "VDD_SDIO_NC_26") (pintype "bidirectional"))
    )
    (net (code "31") (name "Net-(LED1-DI)") (class "Default")
      (node (ref "LED1") (pin "4-DIN") (pinfunction "DI_4-DIN") (pintype "input"))
      (node (ref "R6") (pin "1") (pinfunction "1_1") (pintype "passive"))
    )
    (net (code "32") (name "Net-(Q1A-B)") (class "Default")
      (node (ref "Q1") (pin "5") (pinfunction "B_5") (pintype "passive"))
      (node (ref "R9") (pin "2") (pinfunction "2_2") (pintype "passive"))
    )
    (net (code "33") (name "Net-(Q1B-B)") (class "Default")
      (node (ref "Q1") (pin "2") (pinfunction "B_2") (pintype "passive"))
      (node (ref "R10") (pin "2") (pinfunction "2_2") (pintype "passive"))
    )
    (net (code "34") (name "Net-(U1-USBDM)") (class "Default")
      (node (ref "R14") (pin "2") (pinfunction "2_2") (pintype "passive"))
      (node (ref "U1") (pin "12") (pinfunction "USBDM_12") (pintype "bidirectional"))
    )
    (net (code "35") (name "Net-(U1-USBDP)") (class "Default")
      (node (ref "R15") (pin "2") (pinfunction "2_2") (pintype "passive"))
      (node (ref "U1") (pin "11") (pinfunction "USBDP_11") (pintype "bidirectional"))
    )
    (net (code "36") (name "Net-(U3-PROG)") (class "Default")
      (node (ref "R17") (pin "2") (pinfunction "2_2") (pintype "passive"))
      (node (ref "U3") (pin "5") (pinfunction "PROG_5") (pintype "input"))
    )
    (net (code "37") (name "Net-(U3-STAT)") (class "Default")
      (node (ref "CHG2") (pin "C") (pinfunction "C_C") (pintype "passive"))
      (node (ref "U3") (pin "1") (pinfunction "STAT_1") (pintype "output"))
    )
    (net (code "38") (name "RTS") (class "Default")
      (node (ref "Q1") (pin "4") (pinfunction "E_4") (pintype "passive"))
      (node (ref "R10") (pin "1") (pinfunction "1_1") (pintype "passive"))
      (node (ref "U1") (pin "2") (pinfunction "~{RTS}_2") (pintype "bidirectional"))
    )
    (net (code "39") (name "RXD") (class "Default")
      (node (ref "R13") (pin "2") (pinfunction "2_2") (pintype "passive"))
      (node (ref "U1") (pin "4") (pinfunction "RXD_4") (pintype "bidirectional"))
    )
    (net (code "40") (name "SCL") (class "Default")
      (node (ref "IC1") (pin "42") (pinfunction "IO21_42") (pintype "power_in"))
      (node (ref "J4") (pin "4") (pinfunction "4_4") (pintype "passive"))
      (node (ref "R3") (pin "1") (pinfunction "1_1") (pintype "passive"))
    )
    (net (code "41") (name "SCL1") (class "Default")
      (node (ref "IC1") (pin "14") (pinfunction "IO25_14") (pintype "bidirectional"))
      (node (ref "J1") (pin "4") (pinfunction "4_4") (pintype "passive"))
      (node (ref "R18") (pin "1") (pinfunction "1_1") (pintype "passive"))
    )
    (net (code "42") (name "SDA") (class "Default")
      (node (ref "IC1") (pin "16") (pinfunction "IO27_16") (pintype "bidirectional"))
      (node (ref "J4") (pin "3") (pinfunction "3_3") (pintype "passive"))
      (node (ref "R4") (pin "1") (pinfunction "1_1") (pintype "passive"))
    )
    (net (code "43") (name "SDA1") (class "Default")
      (node (ref "IC1") (pin "15") (pinfunction "IO26_15") (pintype "bidirectional"))
      (node (ref "J1") (pin "3") (pinfunction "3_3") (pintype "passive"))
      (node (ref "R5") (pin "1") (pinfunction "1_1") (pintype "passive"))
    )
    (net (code "44") (name "SENSOR_CAPN") (class "Default")
      (node (ref "IC1") (pin "7") (pinfunction "SENSOR_CAPN_7") (pintype "power_in"))
    )
    (net (code "45") (name "TXD") (class "Default")
      (node (ref "R12") (pin "2") (pinfunction "2_2") (pintype "passive"))
      (node (ref "U1") (pin "20") (pinfunction "TXD_20") (pintype "bidirectional"))
    )
    (net (code "46") (name "U0RXD") (class "Default")
      (node (ref "IC1") (pin "40") (pinfunction "U0RXD_40") (pintype "bidirectional"))
      (node (ref "R12") (pin "1") (pinfunction "1_1") (pintype "passive"))
    )
    (net (code "47") (name "U0TXD") (class "Default")
      (node (ref "IC1") (pin "41") (pinfunction "U0TXD_41") (pintype "bidirectional"))
      (node (ref "R13") (pin "1") (pinfunction "1_1") (pintype "passive"))
    )
    (net (code "48") (name "VBAT") (class "Default")
      (node (ref "C65") (pin "1") (pinfunction "1_1") (pintype "passive"))
      (node (ref "JP6") (pin "2") (pinfunction "2_2") (pintype "passive"))
      (node (ref "Q2") (pin "3") (pinfunction "D_3") (pintype "passive"))
      (node (ref "R25") (pin "2") (pinfunction "2_2") (pintype "passive"))
      (node (ref "U3") (pin "3") (pinfunction "VBAT_3") (pintype "power_in"))
    )
    (net (code "49") (name "VIN") (class "Default")
      (node (ref "C63") (pin "1") (pinfunction "1_1") (pintype "passive"))
      (node (ref "C72") (pin "2") (pinfunction "2_2") (pintype "passive"))
      (node (ref "D1") (pin "C") (pinfunction "C_C") (pintype "passive"))
      (node (ref "Q2") (pin "2") (pinfunction "S_2") (pintype "passive"))
      (node (ref "S2") (pin "3") (pinfunction "S_3") (pintype "passive"))
      (node (ref "U8") (pin "1") (pinfunction "IN_1") (pintype "input"))
    )
    (net (code "50") (name "VUSB") (class "Default")
      (node (ref "C60") (pin "1") (pinfunction "1_1") (pintype "passive"))
      (node (ref "C61") (pin "1") (pinfunction "1_1") (pintype "passive"))
      (node (ref "C64") (pin "1") (pinfunction "1_1") (pintype "passive"))
      (node (ref "D1") (pin "A") (pinfunction "A_A") (pintype "passive"))
      (node (ref "JP7") (pin "1") (pinfunction "VCC_1") (pintype "bidirectional"))
      (node (ref "Q2") (pin "1") (pinfunction "G_1") (pintype "passive"))
      (node (ref "R16") (pin "1") (pinfunction "1_1") (pintype "passive"))
      (node (ref "R23") (pin "2") (pinfunction "2_2") (pintype "passive"))
      (node (ref "U1") (pin "15") (pinfunction "VCC_15") (pintype "bidirectional"))
      (node (ref "U3") (pin "4") (pinfunction "VIN_4") (pintype "power_in"))
    )
    (net (code "51") (name "WS2812") (class "Default")
      (node (ref "IC1") (pin "17") (pinfunction "IO14_17") (pintype "bidirectional"))
      (node (ref "R6") (pin "2") (pinfunction "2_2") (pintype "passive"))
    )
    (net (code "52") (name "unconnected-(IC1A-CAP1_NC-Pad48)") (class "Default")
      (node (ref "IC1") (pin "48") (pinfunction "CAP1_NC_48") (pintype "bidirectional"))
    )
    (net (code "53") (name "unconnected-(IC1A-CAP2_NC-Pad47)") (class "Default")
      (node (ref "IC1") (pin "47") (pinfunction "CAP2_NC_47") (pintype "bidirectional"))
    )
    (net (code "54") (name "unconnected-(IC1A-IO2-Pad22)") (class "Default")
      (node (ref "IC1") (pin "22") (pinfunction "IO2_22") (pintype "bidirectional"))
    )
    (net (code "55") (name "unconnected-(IC1A-IO4-Pad24)") (class "Default")
      (node (ref "IC1") (pin "24") (pinfunction "IO4_24") (pintype "bidirectional"))
    )
    (net (code "56") (name "unconnected-(IC1A-IO5-Pad34)") (class "Default")
      (node (ref "IC1") (pin "34") (pinfunction "IO5_34") (pintype "bidirectional"))
    )
    (net (code "57") (name "unconnected-(IC1A-IO13-Pad20)") (class "Default")
      (node (ref "IC1") (pin "20") (pinfunction "IO13_20") (pintype "bidirectional"))
    )
    (net (code "58") (name "unconnected-(IC1A-IO15-Pad21)") (class "Default")
      (node (ref "IC1") (pin "21") (pinfunction "IO15_21") (pintype "bidirectional"))
    )
    (net (code "59") (name "unconnected-(IC1A-IO16-Pad25)") (class "Default")
      (node (ref "IC1") (pin "25") (pinfunction "IO16_25") (pintype "bidirectional"))
    )
    (net (code "60") (name "unconnected-(IC1A-IO17-Pad27)") (class "Default")
      (node (ref "IC1") (pin "27") (pinfunction "IO17_27") (pintype "bidirectional"))
    )
    (net (code "61") (name "unconnected-(IC1A-IO19-Pad38)") (class "Default")
      (node (ref "IC1") (pin "38") (pinfunction "IO19_38") (pintype "bidirectional"))
    )
    (net (code "62") (name "unconnected-(IC1A-SD0-Pad32)") (class "Default")
      (node (ref "IC1") (pin "32") (pinfunction "SD0_32") (pintype "bidirectional"))
    )
    (net (code "63") (name "unconnected-(IC1A-SD1-Pad33)") (class "Default")
      (node (ref "IC1") (pin "33") (pinfunction "SD1_33") (pintype "bidirectional"))
    )
    (net (code "64") (name "unconnected-(IC1A-SENSOR_CAPP-Pad6)") (class "Default")
      (node (ref "IC1") (pin "6") (pinfunction "SENSOR_CAPP_6") (pintype "bidirectional"))
    )
    (net (code "65") (name "unconnected-(IC1A-XTAL_N_NC-Pad44)") (class "Default")
      (node (ref "IC1") (pin "44") (pinfunction "XTAL_N_NC_44") (pintype "bidirectional"))
    )
    (net (code "66") (name "unconnected-(IC1A-XTAL_P_NC-Pad45)") (class "Default")
      (node (ref "IC1") (pin "45") (pinfunction "XTAL_P_NC_45") (pintype "bidirectional"))
    )
    (net (code "67") (name "unconnected-(JP7-ID-Pad4)") (class "Default")
      (node (ref "JP7") (pin "4") (pinfunction "ID_4") (pintype "bidirectional"))
    )
    (net (code "68") (name "unconnected-(LED1-DO-Pad2-DOUT)") (class "Default")
      (node (ref "LED1") (pin "2-DOUT") (pinfunction "DO_2-DOUT") (pintype "output"))
    )
    (net (code "69") (name "unconnected-(SW2-P1-PadA')") (class "Default")
      (node (ref "SW2") (pin "A'") (pinfunction "P1_A'") (pintype "passive"))
    )
    (net (code "70") (name "unconnected-(TP1-PadTP)") (class "Default")
      (node (ref "TP1") (pin "TP") (pinfunction "TP_TP") (pintype "input"))
    )
    (net (code "71") (name "unconnected-(TP2-PadTP)") (class "Default")
      (node (ref "TP2") (pin "TP") (pinfunction "TP_TP") (pintype "input"))
    )
    (net (code "72") (name "unconnected-(TP3-PadTP)") (class "Default")
      (node (ref "TP3") (pin "TP") (pinfunction "TP_TP") (pintype "input"))
    )
    (net (code "73") (name "unconnected-(TP4-PadTP)") (class "Default")
      (node (ref "TP4") (pin "TP") (pinfunction "TP_TP") (pintype "input"))
    )
    (net (code "74") (name "unconnected-(TP5-PadTP)") (class "Default")
      (node (ref "TP5") (pin "TP") (pinfunction "TP_TP") (pintype "input"))
    )
    (net (code "75") (name "unconnected-(TP6-PadTP)") (class "Default")
      (node (ref "TP6") (pin "TP") (pinfunction "TP_TP") (pintype "input"))
    )
    (net (code "76") (name "unconnected-(TP7-PadTP)") (class "Default")
      (node (ref "TP7") (pin "TP") (pinfunction "TP_TP") (pintype "input"))
    )
    (net (code "77") (name "unconnected-(TP8-PadTP)") (class "Default")
      (node (ref "TP8") (pin "TP") (pinfunction "TP_TP") (pintype "input"))
    )
    (net (code "78") (name "unconnected-(TP9-PadTP)") (class "Default")
      (node (ref "TP9") (pin "TP") (pinfunction "TP_TP") (pintype "input"))
    )
    (net (code "79") (name "unconnected-(TP10-PadTP)") (class "Default")
      (node (ref "TP10") (pin "TP") (pinfunction "TP_TP") (pintype "input"))
    )
    (net (code "80") (name "unconnected-(TP11-PadTP)") (class "Default")
      (node (ref "TP11") (pin "TP") (pinfunction "TP_TP") (pintype "input"))
    )
    (net (code "81") (name "unconnected-(TP12-PadTP)") (class "Default")
      (node (ref "TP12") (pin "TP") (pinfunction "TP_TP") (pintype "input"))
    )
    (net (code "82") (name "unconnected-(TP13-PadTP)") (class "Default")
      (node (ref "TP13") (pin "TP") (pinfunction "TP_TP") (pintype "input"))
    )
    (net (code "83") (name "unconnected-(TP14-PadTP)") (class "Default")
      (node (ref "TP14") (pin "TP") (pinfunction "TP_TP") (pintype "input"))
    )
    (net (code "84") (name "unconnected-(TP15-PadTP)") (class "Default")
      (node (ref "TP15") (pin "TP") (pinfunction "TP_TP") (pintype "input"))
    )
    (net (code "85") (name "unconnected-(TP16-PadTP)") (class "Default")
      (node (ref "TP16") (pin "TP") (pinfunction "TP_TP") (pintype "input"))
    )
    (net (code "86") (name "unconnected-(TP17-PadTP)") (class "Default")
      (node (ref "TP17") (pin "TP") (pinfunction "TP_TP") (pintype "input"))
    )
    (net (code "87") (name "unconnected-(TP18-PadTP)") (class "Default")
      (node (ref "TP18") (pin "TP") (pinfunction "TP_TP") (pintype "input"))
    )
    (net (code "88") (name "unconnected-(TP19-PadTP)") (class "Default")
      (node (ref "TP19") (pin "TP") (pinfunction "TP_TP") (pintype "input"))
    )
    (net (code "89") (name "unconnected-(TP20-PadTP)") (class "Default")
      (node (ref "TP20") (pin "TP") (pinfunction "TP_TP") (pintype "input"))
    )
    (net (code "90") (name "unconnected-(TP21-PadTP)") (class "Default")
      (node (ref "TP21") (pin "TP") (pinfunction "TP_TP") (pintype "input"))
    )
    (net (code "91") (name "unconnected-(TP22-PadTP)") (class "Default")
      (node (ref "TP22") (pin "TP") (pinfunction "TP_TP") (pintype "input"))
    )
    (net (code "92") (name "unconnected-(TP23-PadTP)") (class "Default")
      (node (ref "TP23") (pin "TP") (pinfunction "TP_TP") (pintype "input"))
    )
    (net (code "93") (name "unconnected-(TP24-PadTP)") (class "Default")
      (node (ref "TP24") (pin "TP") (pinfunction "TP_TP") (pintype "input"))
    )
    (net (code "94") (name "unconnected-(TP25-PadTP)") (class "Default")
      (node (ref "TP25") (pin "TP") (pinfunction "TP_TP") (pintype "input"))
    )
    (net (code "95") (name "unconnected-(TP26-PadTP)") (class "Default")
      (node (ref "TP26") (pin "TP") (pinfunction "TP_TP") (pintype "input"))
    )
    (net (code "96") (name "unconnected-(TP27-PadTP)") (class "Default")
      (node (ref "TP27") (pin "TP") (pinfunction "TP_TP") (pintype "input"))
    )
    (net (code "97") (name "unconnected-(TP28-PadTP)") (class "Default")
      (node (ref "TP28") (pin "TP") (pinfunction "TP_TP") (pintype "input"))
    )
    (net (code "98") (name "unconnected-(TP29-PadTP)") (class "Default")
      (node (ref "TP29") (pin "TP") (pinfunction "TP_TP") (pintype "input"))
    )
    (net (code "99") (name "unconnected-(TP30-PadTP)") (class "Default")
      (node (ref "TP30") (pin "TP") (pinfunction "TP_TP") (pintype "input"))
    )
    (net (code "100") (name "unconnected-(TP31-PadTP)") (class "Default")
      (node (ref "TP31") (pin "TP") (pinfunction "TP_TP") (pintype "input"))
    )
    (net (code "101") (name "unconnected-(TP32-PadTP)") (class "Default")
      (node (ref "TP32") (pin "TP") (pinfunction "TP_TP") (pintype "input"))
    )
    (net (code "102") (name "unconnected-(TP33-PadTP)") (class "Default")
      (node (ref "TP33") (pin "TP") (pinfunction "TP_TP") (pintype "input"))
    )
    (net (code "103") (name "unconnected-(TP34-PadTP)") (class "Default")
      (node (ref "TP34") (pin "TP") (pinfunction "TP_TP") (pintype "input"))
    )
    (net (code "104") (name "unconnected-(TP35-PadTP)") (class "Default")
      (node (ref "TP35") (pin "TP") (pinfunction "TP_TP") (pintype "input"))
    )
    (net (code "105") (name "unconnected-(TP36-PadTP)") (class "Default")
      (node (ref "TP36") (pin "TP") (pinfunction "TP_TP") (pintype "input"))
    )
    (net (code "106") (name "unconnected-(TP37-PadTP)") (class "Default")
      (node (ref "TP37") (pin "TP") (pinfunction "TP_TP") (pintype "input"))
    )
    (net (code "107") (name "unconnected-(TP38-PadTP)") (class "Default")
      (node (ref "TP38") (pin "TP") (pinfunction "TP_TP") (pintype "input"))
    )
    (net (code "108") (name "unconnected-(TP39-PadTP)") (class "Default")
      (node (ref "TP39") (pin "TP") (pinfunction "TP_TP") (pintype "input"))
    )
    (net (code "109") (name "unconnected-(TP40-PadTP)") (class "Default")
      (node (ref "TP40") (pin "TP") (pinfunction "TP_TP") (pintype "input"))
    )
    (net (code "110") (name "unconnected-(TP41-PadTP)") (class "Default")
      (node (ref "TP41") (pin "TP") (pinfunction "TP_TP") (pintype "input"))
    )
    (net (code "111") (name "unconnected-(TP42-PadTP)") (class "Default")
      (node (ref "TP42") (pin "TP") (pinfunction "TP_TP") (pintype "input"))
    )
    (net (code "112") (name "unconnected-(TP43-PadTP)") (class "Default")
      (node (ref "TP43") (pin "TP") (pinfunction "TP_TP") (pintype "input"))
    )
    (net (code "113") (name "unconnected-(TP44-PadTP)") (class "Default")
      (node (ref "TP44") (pin "TP") (pinfunction "TP_TP") (pintype "input"))
    )
    (net (code "114") (name "unconnected-(TP45-PadTP)") (class "Default")
      (node (ref "TP45") (pin "TP") (pinfunction "TP_TP") (pintype "input"))
    )
    (net (code "115") (name "unconnected-(TP46-PadTP)") (class "Default")
      (node (ref "TP46") (pin "TP") (pinfunction "TP_TP") (pintype "input"))
    )
    (net (code "116") (name "unconnected-(TP47-PadTP)") (class "Default")
      (node (ref "TP47") (pin "TP") (pinfunction "TP_TP") (pintype "input"))
    )
    (net (code "117") (name "unconnected-(TP48-PadTP)") (class "Default")
      (node (ref "TP48") (pin "TP") (pinfunction "TP_TP") (pintype "input"))
    )
    (net (code "118") (name "unconnected-(TP49-PadTP)") (class "Default")
      (node (ref "TP49") (pin "TP") (pinfunction "TP_TP") (pintype "input"))
    )
    (net (code "119") (name "unconnected-(TP50-PadTP)") (class "Default")
      (node (ref "TP50") (pin "TP") (pinfunction "TP_TP") (pintype "input"))
    )
    (net (code "120") (name "unconnected-(TP51-PadTP)") (class "Default")
      (node (ref "TP51") (pin "TP") (pinfunction "TP_TP") (pintype "input"))
    )
    (net (code "121") (name "unconnected-(TP52-PadTP)") (class "Default")
      (node (ref "TP52") (pin "TP") (pinfunction "TP_TP") (pintype "input"))
    )
    (net (code "122") (name "unconnected-(TP53-PadTP)") (class "Default")
      (node (ref "TP53") (pin "TP") (pinfunction "TP_TP") (pintype "input"))
    )
    (net (code "123") (name "unconnected-(TP54-PadTP)") (class "Default")
      (node (ref "TP54") (pin "TP") (pinfunction "TP_TP") (pintype "input"))
    )
    (net (code "124") (name "unconnected-(TP55-PadTP)") (class "Default")
      (node (ref "TP55") (pin "TP") (pinfunction "TP_TP") (pintype "input"))
    )
    (net (code "125") (name "unconnected-(TP56-PadTP)") (class "Default")
      (node (ref "TP56") (pin "TP") (pinfunction "TP_TP") (pintype "input"))
    )
    (net (code "126") (name "unconnected-(TP57-PadTP)") (class "Default")
      (node (ref "TP57") (pin "TP") (pinfunction "TP_TP") (pintype "input"))
    )
    (net (code "127") (name "unconnected-(TP58-PadTP)") (class "Default")
      (node (ref "TP58") (pin "TP") (pinfunction "TP_TP") (pintype "input"))
    )
    (net (code "128") (name "unconnected-(TP59-PadTP)") (class "Default")
      (node (ref "TP59") (pin "TP") (pinfunction "TP_TP") (pintype "input"))
    )
    (net (code "129") (name "unconnected-(TP60-PadTP)") (class "Default")
      (node (ref "TP60") (pin "TP") (pinfunction "TP_TP") (pintype "input"))
    )
    (net (code "130") (name "unconnected-(TP61-PadTP)") (class "Default")
      (node (ref "TP61") (pin "TP") (pinfunction "TP_TP") (pintype "input"))
    )
    (net (code "131") (name "unconnected-(TP62-PadTP)") (class "Default")
      (node (ref "TP62") (pin "TP") (pinfunction "TP_TP") (pintype "input"))
    )
    (net (code "132") (name "unconnected-(TP63-PadTP)") (class "Default")
      (node (ref "TP63") (pin "TP") (pinfunction "TP_TP") (pintype "input"))
    )
    (net (code "133") (name "unconnected-(TP64-PadTP)") (class "Default")
      (node (ref "TP64") (pin "TP") (pinfunction "TP_TP") (pintype "input"))
    )
    (net (code "134") (name "unconnected-(TP65-PadTP)") (class "Default")
      (node (ref "TP65") (pin "TP") (pinfunction "TP_TP") (pintype "input"))
    )
    (net (code "135") (name "unconnected-(TP66-PadTP)") (class "Default")
      (node (ref "TP66") (pin "TP") (pinfunction "TP_TP") (pintype "input"))
    )
    (net (code "136") (name "unconnected-(TP67-PadTP)") (class "Default")
      (node (ref "TP67") (pin "TP") (pinfunction "TP_TP") (pintype "input"))
    )
    (net (code "137") (name "unconnected-(TP68-PadTP)") (class "Default")
      (node (ref "TP68") (pin "TP") (pinfunction "TP_TP") (pintype "input"))
    )
    (net (code "138") (name "unconnected-(TP69-PadTP)") (class "Default")
      (node (ref "TP69") (pin "TP") (pinfunction "TP_TP") (pintype "input"))
    )
    (net (code "139") (name "unconnected-(TP70-PadTP)") (class "Default")
      (node (ref "TP70") (pin "TP") (pinfunction "TP_TP") (pintype "input"))
    )
    (net (code "140") (name "unconnected-(TP71-PadTP)") (class "Default")
      (node (ref "TP71") (pin "TP") (pinfunction "TP_TP") (pintype "input"))
    )
    (net (code "141") (name "unconnected-(TP72-PadTP)") (class "Default")
      (node (ref "TP72") (pin "TP") (pinfunction "TP_TP") (pintype "input"))
    )
    (net (code "142") (name "unconnected-(TP73-PadTP)") (class "Default")
      (node (ref "TP73") (pin "TP") (pinfunction "TP_TP") (pintype "input"))
    )
    (net (code "143") (name "unconnected-(TP74-PadTP)") (class "Default")
      (node (ref "TP74") (pin "TP") (pinfunction "TP_TP") (pintype "input"))
    )
    (net (code "144") (name "unconnected-(TP75-PadTP)") (class "Default")
      (node (ref "TP75") (pin "TP") (pinfunction "TP_TP") (pintype "input"))
    )
    (net (code "145") (name "unconnected-(TP76-PadTP)") (class "Default")
      (node (ref "TP76") (pin "TP") (pinfunction "TP_TP") (pintype "input"))
    )
    (net (code "146") (name "unconnected-(TP77-PadTP)") (class "Default")
      (node (ref "TP77") (pin "TP") (pinfunction "TP_TP") (pintype "input"))
    )
    (net (code "147") (name "unconnected-(TP78-PadTP)") (class "Default")
      (node (ref "TP78") (pin "TP") (pinfunction "TP_TP") (pintype "input"))
    )
    (net (code "148") (name "unconnected-(TP79-PadTP)") (class "Default")
      (node (ref "TP79") (pin "TP") (pinfunction "TP_TP") (pintype "input"))
    )
    (net (code "149") (name "unconnected-(TP80-PadTP)") (class "Default")
      (node (ref "TP80") (pin "TP") (pinfunction "TP_TP") (pintype "input"))
    )
    (net (code "150") (name "unconnected-(TP81-PadTP)") (class "Default")
      (node (ref "TP81") (pin "TP") (pinfunction "TP_TP") (pintype "input"))
    )
    (net (code "151") (name "unconnected-(TP82-PadTP)") (class "Default")
      (node (ref "TP82") (pin "TP") (pinfunction "TP_TP") (pintype "input"))
    )
    (net (code "152") (name "unconnected-(TP83-PadTP)") (class "Default")
      (node (ref "TP83") (pin "TP") (pinfunction "TP_TP") (pintype "input"))
    )
    (net (code "153") (name "unconnected-(TP84-PadTP)") (class "Default")
      (node (ref "TP84") (pin "TP") (pinfunction "TP_TP") (pintype "input"))
    )
    (net (code "154") (name "unconnected-(U1-CBUS0-Pad18)") (class "Default")
      (node (ref "U1") (pin "18") (pinfunction "CBUS0_18") (pintype "bidirectional"))
    )
    (net (code "155") (name "unconnected-(U1-CBUS1-Pad17)") (class "Default")
      (node (ref "U1") (pin "17") (pinfunction "CBUS1_17") (pintype "bidirectional"))
    )
    (net (code "156") (name "unconnected-(U1-CBUS2-Pad10)") (class "Default")
      (node (ref "U1") (pin "10") (pinfunction "CBUS2_10") (pintype "bidirectional"))
    )
    (net (code "157") (name "unconnected-(U1-CBUS3-Pad19)") (class "Default")
      (node (ref "U1") (pin "19") (pinfunction "CBUS3_19") (pintype "bidirectional"))
    )
    (net (code "158") (name "unconnected-(U1-~{CTS}-Pad9)") (class "Default")
      (node (ref "U1") (pin "9") (pinfunction "~{CTS}_9") (pintype "bidirectional"))
    )
    (net (code "159") (name "unconnected-(U1-~{DCD}-Pad8)") (class "Default")
      (node (ref "U1") (pin "8") (pinfunction "~{DCD}_8") (pintype "bidirectional"))
    )
    (net (code "160") (name "unconnected-(U1-~{DSR}-Pad7)") (class "Default")
      (node (ref "U1") (pin "7") (pinfunction "~{DSR}_7") (pintype "bidirectional"))
    )
    (net (code "161") (name "unconnected-(U1-~{RI}-Pad5)") (class "Default")
      (node (ref "U1") (pin "5") (pinfunction "~{RI}_5") (pintype "bidirectional"))
    )
    (net (code "162") (name "unconnected-(U8-BP-Pad4)") (class "Default")
      (node (ref "U8") (pin "4") (pinfunction "BP_4") (pintype "input"))
    )
  )
)
